# Connector_1.net
KiCad netlist of a schematic drawn in Altium Designer
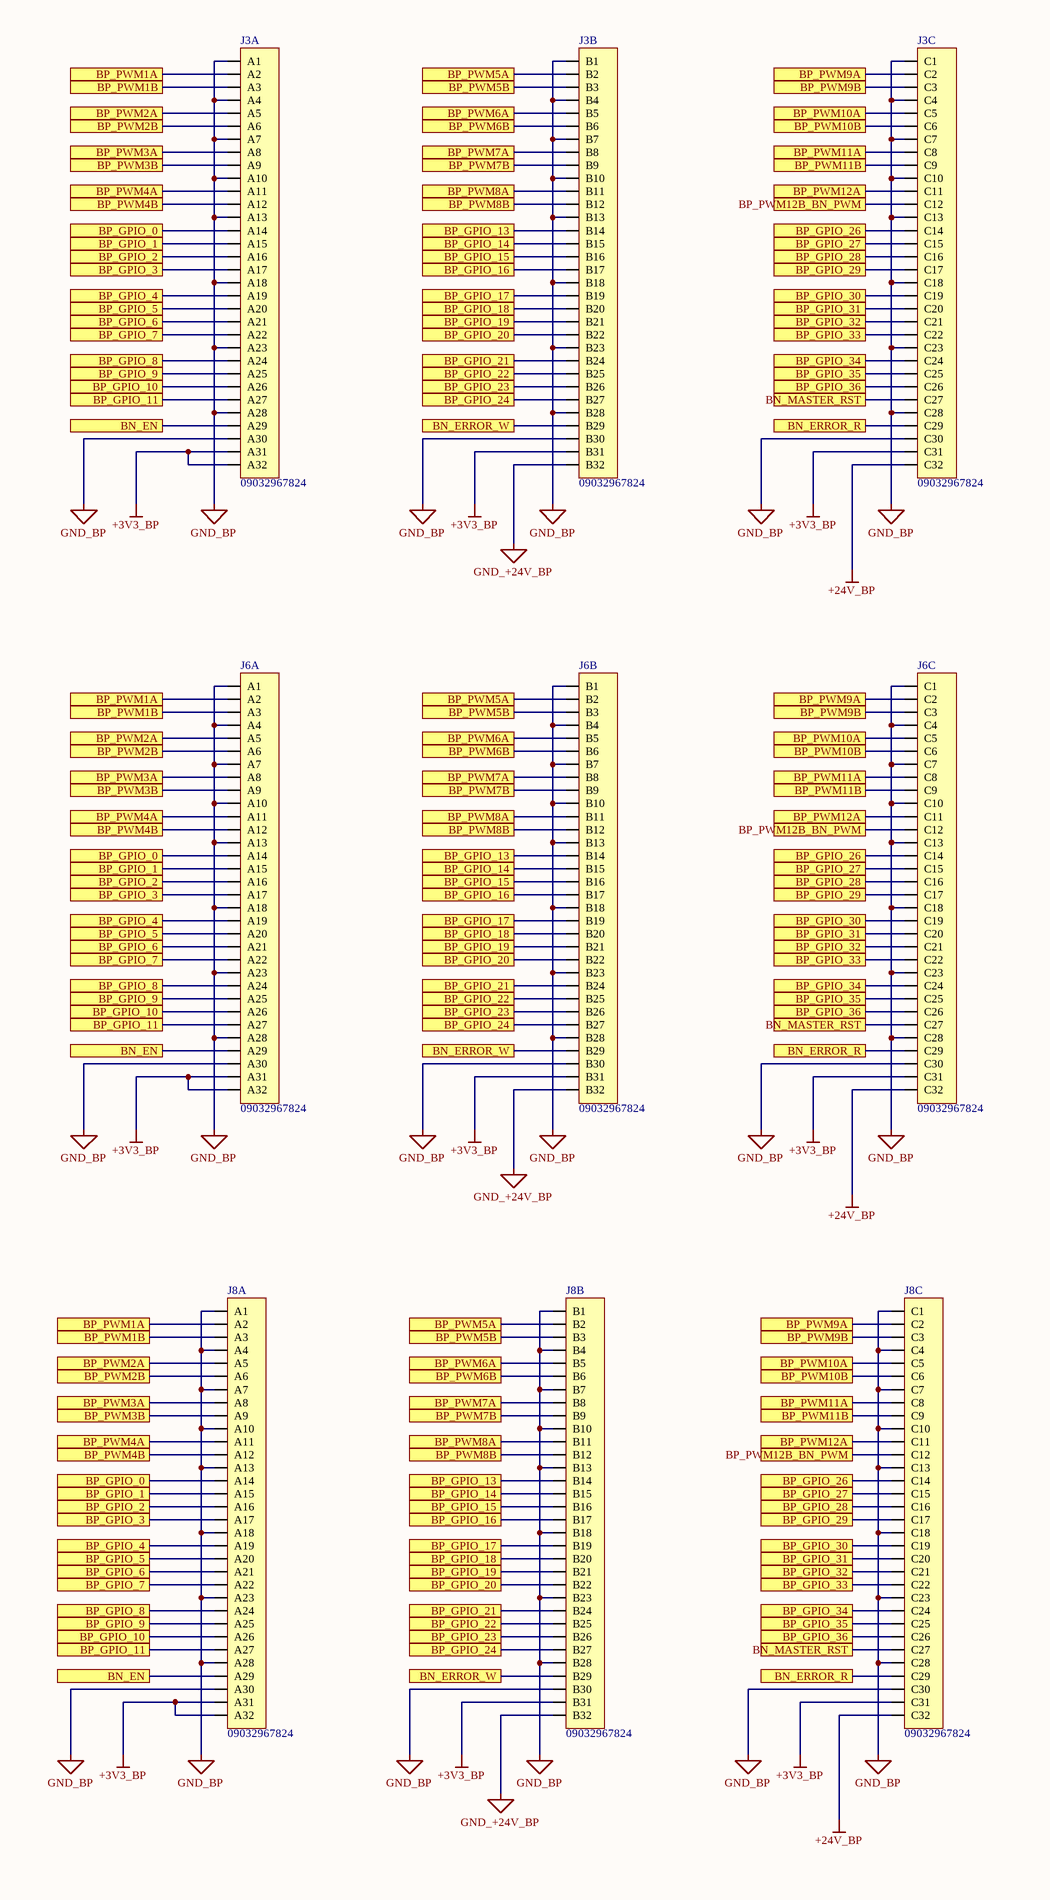
[diagram p0: Connector_1.SchDoc, left]
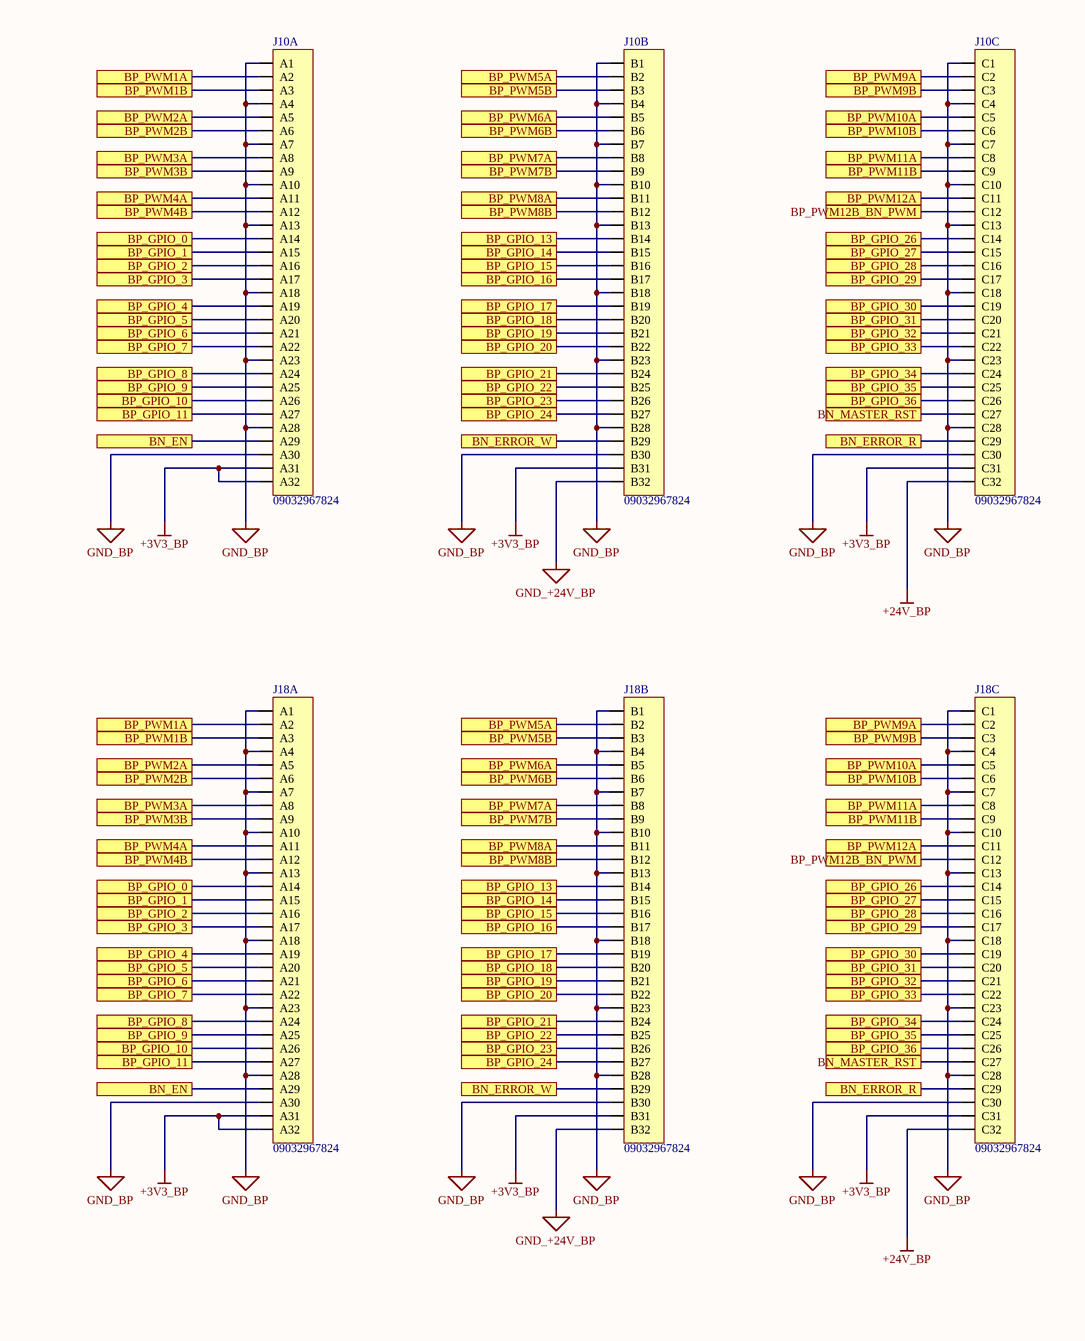
[diagram p1: Connector_1.SchDoc, right]

(export (version "E")
  (design (tool "Eeschema 10.0.6"))
  (components
    (comp (ref "J3")
      (value "09032967824")
      (footprint "DIN41612 FEM 3x32 ABC Straight")
      (description "DIN41612 FEM 3X32 ABC STRAIGHT")
      (fields (field (name "MANUFACTURER") "Harting"))
      (libsource (lib "Connector") (part "DIN41612 FEM 3X32 STRAIGHT"))
    )
    (comp (ref "J6")
      (value "09032967824")
      (footprint "DIN41612 FEM 3x32 ABC Straight")
      (description "DIN41612 FEM 3X32 ABC STRAIGHT")
      (fields (field (name "MANUFACTURER") "Harting"))
      (libsource (lib "Connector") (part "DIN41612 FEM 3X32 STRAIGHT"))
    )
    (comp (ref "J8")
      (value "09032967824")
      (footprint "DIN41612 FEM 3x32 ABC Straight")
      (description "DIN41612 FEM 3X32 ABC STRAIGHT")
      (fields (field (name "MANUFACTURER") "Harting"))
      (libsource (lib "Connector") (part "DIN41612 FEM 3X32 STRAIGHT"))
    )
    (comp (ref "J10")
      (value "09032967824")
      (footprint "DIN41612 FEM 3x32 ABC Straight")
      (description "DIN41612 FEM 3X32 ABC STRAIGHT")
      (fields (field (name "MANUFACTURER") "Harting"))
      (libsource (lib "Connector") (part "DIN41612 FEM 3X32 STRAIGHT"))
    )
    (comp (ref "J18")
      (value "09032967824")
      (footprint "DIN41612 FEM 3x32 ABC Straight")
      (description "DIN41612 FEM 3X32 ABC STRAIGHT")
      (fields (field (name "MANUFACTURER") "Harting"))
      (libsource (lib "Connector") (part "DIN41612 FEM 3X32 STRAIGHT"))
    )
  )
  (nets
    (net (code "1") (name "+3V3_BP") (class "Default")
      (node (ref "J10") (pin "A31") (pinfunction "A31_A31") (pintype "passive"))
      (node (ref "J10") (pin "A32") (pinfunction "A32_A32") (pintype "passive"))
      (node (ref "J10") (pin "B31") (pinfunction "B31_B31") (pintype "passive"))
      (node (ref "J10") (pin "C31") (pinfunction "C31_C31") (pintype "passive"))
      (node (ref "J18") (pin "A31") (pinfunction "A31_A31") (pintype "passive"))
      (node (ref "J18") (pin "A32") (pinfunction "A32_A32") (pintype "passive"))
      (node (ref "J18") (pin "B31") (pinfunction "B31_B31") (pintype "passive"))
      (node (ref "J18") (pin "C31") (pinfunction "C31_C31") (pintype "passive"))
      (node (ref "J3") (pin "A31") (pinfunction "A31_A31") (pintype "passive"))
      (node (ref "J3") (pin "A32") (pinfunction "A32_A32") (pintype "passive"))
      (node (ref "J3") (pin "B31") (pinfunction "B31_B31") (pintype "passive"))
      (node (ref "J3") (pin "C31") (pinfunction "C31_C31") (pintype "passive"))
      (node (ref "J6") (pin "A31") (pinfunction "A31_A31") (pintype "passive"))
      (node (ref "J6") (pin "A32") (pinfunction "A32_A32") (pintype "passive"))
      (node (ref "J6") (pin "B31") (pinfunction "B31_B31") (pintype "passive"))
      (node (ref "J6") (pin "C31") (pinfunction "C31_C31") (pintype "passive"))
      (node (ref "J8") (pin "A31") (pinfunction "A31_A31") (pintype "passive"))
      (node (ref "J8") (pin "A32") (pinfunction "A32_A32") (pintype "passive"))
      (node (ref "J8") (pin "B31") (pinfunction "B31_B31") (pintype "passive"))
      (node (ref "J8") (pin "C31") (pinfunction "C31_C31") (pintype "passive"))
    )
    (net (code "2") (name "+24V_BP") (class "Default")
      (node (ref "J10") (pin "C32") (pinfunction "C32_C32") (pintype "passive"))
      (node (ref "J18") (pin "C32") (pinfunction "C32_C32") (pintype "passive"))
      (node (ref "J3") (pin "C32") (pinfunction "C32_C32") (pintype "passive"))
      (node (ref "J6") (pin "C32") (pinfunction "C32_C32") (pintype "passive"))
      (node (ref "J8") (pin "C32") (pinfunction "C32_C32") (pintype "passive"))
    )
    (net (code "3") (name "/BN_EN") (class "Default")
      (node (ref "J10") (pin "A29") (pinfunction "A29_A29") (pintype "passive"))
      (node (ref "J18") (pin "A29") (pinfunction "A29_A29") (pintype "passive"))
      (node (ref "J3") (pin "A29") (pinfunction "A29_A29") (pintype "passive"))
      (node (ref "J6") (pin "A29") (pinfunction "A29_A29") (pintype "passive"))
      (node (ref "J8") (pin "A29") (pinfunction "A29_A29") (pintype "passive"))
    )
    (net (code "4") (name "/BN_ERROR_R") (class "Default")
      (node (ref "J10") (pin "C29") (pinfunction "C29_C29") (pintype "passive"))
      (node (ref "J18") (pin "C29") (pinfunction "C29_C29") (pintype "passive"))
      (node (ref "J3") (pin "C29") (pinfunction "C29_C29") (pintype "passive"))
      (node (ref "J6") (pin "C29") (pinfunction "C29_C29") (pintype "passive"))
      (node (ref "J8") (pin "C29") (pinfunction "C29_C29") (pintype "passive"))
    )
    (net (code "5") (name "/BN_ERROR_W") (class "Default")
      (node (ref "J10") (pin "B29") (pinfunction "B29_B29") (pintype "passive"))
      (node (ref "J18") (pin "B29") (pinfunction "B29_B29") (pintype "passive"))
      (node (ref "J3") (pin "B29") (pinfunction "B29_B29") (pintype "passive"))
      (node (ref "J6") (pin "B29") (pinfunction "B29_B29") (pintype "passive"))
      (node (ref "J8") (pin "B29") (pinfunction "B29_B29") (pintype "passive"))
    )
    (net (code "6") (name "/BN_MASTER_RST") (class "Default")
      (node (ref "J10") (pin "C27") (pinfunction "C27_C27") (pintype "passive"))
      (node (ref "J18") (pin "C27") (pinfunction "C27_C27") (pintype "passive"))
      (node (ref "J3") (pin "C27") (pinfunction "C27_C27") (pintype "passive"))
      (node (ref "J6") (pin "C27") (pinfunction "C27_C27") (pintype "passive"))
      (node (ref "J8") (pin "C27") (pinfunction "C27_C27") (pintype "passive"))
    )
    (net (code "7") (name "/BP_GPIO_0") (class "Default")
      (node (ref "J10") (pin "A14") (pinfunction "A14_A14") (pintype "passive"))
      (node (ref "J18") (pin "A14") (pinfunction "A14_A14") (pintype "passive"))
      (node (ref "J3") (pin "A14") (pinfunction "A14_A14") (pintype "passive"))
      (node (ref "J6") (pin "A14") (pinfunction "A14_A14") (pintype "passive"))
      (node (ref "J8") (pin "A14") (pinfunction "A14_A14") (pintype "passive"))
    )
    (net (code "8") (name "/BP_GPIO_1") (class "Default")
      (node (ref "J10") (pin "A15") (pinfunction "A15_A15") (pintype "passive"))
      (node (ref "J18") (pin "A15") (pinfunction "A15_A15") (pintype "passive"))
      (node (ref "J3") (pin "A15") (pinfunction "A15_A15") (pintype "passive"))
      (node (ref "J6") (pin "A15") (pinfunction "A15_A15") (pintype "passive"))
      (node (ref "J8") (pin "A15") (pinfunction "A15_A15") (pintype "passive"))
    )
    (net (code "9") (name "/BP_GPIO_2") (class "Default")
      (node (ref "J10") (pin "A16") (pinfunction "A16_A16") (pintype "passive"))
      (node (ref "J18") (pin "A16") (pinfunction "A16_A16") (pintype "passive"))
      (node (ref "J3") (pin "A16") (pinfunction "A16_A16") (pintype "passive"))
      (node (ref "J6") (pin "A16") (pinfunction "A16_A16") (pintype "passive"))
      (node (ref "J8") (pin "A16") (pinfunction "A16_A16") (pintype "passive"))
    )
    (net (code "10") (name "/BP_GPIO_3") (class "Default")
      (node (ref "J10") (pin "A17") (pinfunction "A17_A17") (pintype "passive"))
      (node (ref "J18") (pin "A17") (pinfunction "A17_A17") (pintype "passive"))
      (node (ref "J3") (pin "A17") (pinfunction "A17_A17") (pintype "passive"))
      (node (ref "J6") (pin "A17") (pinfunction "A17_A17") (pintype "passive"))
      (node (ref "J8") (pin "A17") (pinfunction "A17_A17") (pintype "passive"))
    )
    (net (code "11") (name "/BP_GPIO_4") (class "Default")
      (node (ref "J10") (pin "A19") (pinfunction "A19_A19") (pintype "passive"))
      (node (ref "J18") (pin "A19") (pinfunction "A19_A19") (pintype "passive"))
      (node (ref "J3") (pin "A19") (pinfunction "A19_A19") (pintype "passive"))
      (node (ref "J6") (pin "A19") (pinfunction "A19_A19") (pintype "passive"))
      (node (ref "J8") (pin "A19") (pinfunction "A19_A19") (pintype "passive"))
    )
    (net (code "12") (name "/BP_GPIO_5") (class "Default")
      (node (ref "J10") (pin "A20") (pinfunction "A20_A20") (pintype "passive"))
      (node (ref "J18") (pin "A20") (pinfunction "A20_A20") (pintype "passive"))
      (node (ref "J3") (pin "A20") (pinfunction "A20_A20") (pintype "passive"))
      (node (ref "J6") (pin "A20") (pinfunction "A20_A20") (pintype "passive"))
      (node (ref "J8") (pin "A20") (pinfunction "A20_A20") (pintype "passive"))
    )
    (net (code "13") (name "/BP_GPIO_6") (class "Default")
      (node (ref "J10") (pin "A21") (pinfunction "A21_A21") (pintype "passive"))
      (node (ref "J18") (pin "A21") (pinfunction "A21_A21") (pintype "passive"))
      (node (ref "J3") (pin "A21") (pinfunction "A21_A21") (pintype "passive"))
      (node (ref "J6") (pin "A21") (pinfunction "A21_A21") (pintype "passive"))
      (node (ref "J8") (pin "A21") (pinfunction "A21_A21") (pintype "passive"))
    )
    (net (code "14") (name "/BP_GPIO_7") (class "Default")
      (node (ref "J10") (pin "A22") (pinfunction "A22_A22") (pintype "passive"))
      (node (ref "J18") (pin "A22") (pinfunction "A22_A22") (pintype "passive"))
      (node (ref "J3") (pin "A22") (pinfunction "A22_A22") (pintype "passive"))
      (node (ref "J6") (pin "A22") (pinfunction "A22_A22") (pintype "passive"))
      (node (ref "J8") (pin "A22") (pinfunction "A22_A22") (pintype "passive"))
    )
    (net (code "15") (name "/BP_GPIO_8") (class "Default")
      (node (ref "J10") (pin "A24") (pinfunction "A24_A24") (pintype "passive"))
      (node (ref "J18") (pin "A24") (pinfunction "A24_A24") (pintype "passive"))
      (node (ref "J3") (pin "A24") (pinfunction "A24_A24") (pintype "passive"))
      (node (ref "J6") (pin "A24") (pinfunction "A24_A24") (pintype "passive"))
      (node (ref "J8") (pin "A24") (pinfunction "A24_A24") (pintype "passive"))
    )
    (net (code "16") (name "/BP_GPIO_9") (class "Default")
      (node (ref "J10") (pin "A25") (pinfunction "A25_A25") (pintype "passive"))
      (node (ref "J18") (pin "A25") (pinfunction "A25_A25") (pintype "passive"))
      (node (ref "J3") (pin "A25") (pinfunction "A25_A25") (pintype "passive"))
      (node (ref "J6") (pin "A25") (pinfunction "A25_A25") (pintype "passive"))
      (node (ref "J8") (pin "A25") (pinfunction "A25_A25") (pintype "passive"))
    )
    (net (code "17") (name "/BP_GPIO_10") (class "Default")
      (node (ref "J10") (pin "A26") (pinfunction "A26_A26") (pintype "passive"))
      (node (ref "J18") (pin "A26") (pinfunction "A26_A26") (pintype "passive"))
      (node (ref "J3") (pin "A26") (pinfunction "A26_A26") (pintype "passive"))
      (node (ref "J6") (pin "A26") (pinfunction "A26_A26") (pintype "passive"))
      (node (ref "J8") (pin "A26") (pinfunction "A26_A26") (pintype "passive"))
    )
    (net (code "18") (name "/BP_GPIO_11") (class "Default")
      (node (ref "J10") (pin "A27") (pinfunction "A27_A27") (pintype "passive"))
      (node (ref "J18") (pin "A27") (pinfunction "A27_A27") (pintype "passive"))
      (node (ref "J3") (pin "A27") (pinfunction "A27_A27") (pintype "passive"))
      (node (ref "J6") (pin "A27") (pinfunction "A27_A27") (pintype "passive"))
      (node (ref "J8") (pin "A27") (pinfunction "A27_A27") (pintype "passive"))
    )
    (net (code "19") (name "/BP_GPIO_13") (class "Default")
      (node (ref "J10") (pin "B14") (pinfunction "B14_B14") (pintype "passive"))
      (node (ref "J18") (pin "B14") (pinfunction "B14_B14") (pintype "passive"))
      (node (ref "J3") (pin "B14") (pinfunction "B14_B14") (pintype "passive"))
      (node (ref "J6") (pin "B14") (pinfunction "B14_B14") (pintype "passive"))
      (node (ref "J8") (pin "B14") (pinfunction "B14_B14") (pintype "passive"))
    )
    (net (code "20") (name "/BP_GPIO_14") (class "Default")
      (node (ref "J10") (pin "B15") (pinfunction "B15_B15") (pintype "passive"))
      (node (ref "J18") (pin "B15") (pinfunction "B15_B15") (pintype "passive"))
      (node (ref "J3") (pin "B15") (pinfunction "B15_B15") (pintype "passive"))
      (node (ref "J6") (pin "B15") (pinfunction "B15_B15") (pintype "passive"))
      (node (ref "J8") (pin "B15") (pinfunction "B15_B15") (pintype "passive"))
    )
    (net (code "21") (name "/BP_GPIO_15") (class "Default")
      (node (ref "J10") (pin "B16") (pinfunction "B16_B16") (pintype "passive"))
      (node (ref "J18") (pin "B16") (pinfunction "B16_B16") (pintype "passive"))
      (node (ref "J3") (pin "B16") (pinfunction "B16_B16") (pintype "passive"))
      (node (ref "J6") (pin "B16") (pinfunction "B16_B16") (pintype "passive"))
      (node (ref "J8") (pin "B16") (pinfunction "B16_B16") (pintype "passive"))
    )
    (net (code "22") (name "/BP_GPIO_16") (class "Default")
      (node (ref "J10") (pin "B17") (pinfunction "B17_B17") (pintype "passive"))
      (node (ref "J18") (pin "B17") (pinfunction "B17_B17") (pintype "passive"))
      (node (ref "J3") (pin "B17") (pinfunction "B17_B17") (pintype "passive"))
      (node (ref "J6") (pin "B17") (pinfunction "B17_B17") (pintype "passive"))
      (node (ref "J8") (pin "B17") (pinfunction "B17_B17") (pintype "passive"))
    )
    (net (code "23") (name "/BP_GPIO_17") (class "Default")
      (node (ref "J10") (pin "B19") (pinfunction "B19_B19") (pintype "passive"))
      (node (ref "J18") (pin "B19") (pinfunction "B19_B19") (pintype "passive"))
      (node (ref "J3") (pin "B19") (pinfunction "B19_B19") (pintype "passive"))
      (node (ref "J6") (pin "B19") (pinfunction "B19_B19") (pintype "passive"))
      (node (ref "J8") (pin "B19") (pinfunction "B19_B19") (pintype "passive"))
    )
    (net (code "24") (name "/BP_GPIO_18") (class "Default")
      (node (ref "J10") (pin "B20") (pinfunction "B20_B20") (pintype "passive"))
      (node (ref "J18") (pin "B20") (pinfunction "B20_B20") (pintype "passive"))
      (node (ref "J3") (pin "B20") (pinfunction "B20_B20") (pintype "passive"))
      (node (ref "J6") (pin "B20") (pinfunction "B20_B20") (pintype "passive"))
      (node (ref "J8") (pin "B20") (pinfunction "B20_B20") (pintype "passive"))
    )
    (net (code "25") (name "/BP_GPIO_19") (class "Default")
      (node (ref "J10") (pin "B21") (pinfunction "B21_B21") (pintype "passive"))
      (node (ref "J18") (pin "B21") (pinfunction "B21_B21") (pintype "passive"))
      (node (ref "J3") (pin "B21") (pinfunction "B21_B21") (pintype "passive"))
      (node (ref "J6") (pin "B21") (pinfunction "B21_B21") (pintype "passive"))
      (node (ref "J8") (pin "B21") (pinfunction "B21_B21") (pintype "passive"))
    )
    (net (code "26") (name "/BP_GPIO_20") (class "Default")
      (node (ref "J10") (pin "B22") (pinfunction "B22_B22") (pintype "passive"))
      (node (ref "J18") (pin "B22") (pinfunction "B22_B22") (pintype "passive"))
      (node (ref "J3") (pin "B22") (pinfunction "B22_B22") (pintype "passive"))
      (node (ref "J6") (pin "B22") (pinfunction "B22_B22") (pintype "passive"))
      (node (ref "J8") (pin "B22") (pinfunction "B22_B22") (pintype "passive"))
    )
    (net (code "27") (name "/BP_GPIO_21") (class "Default")
      (node (ref "J10") (pin "B24") (pinfunction "B24_B24") (pintype "passive"))
      (node (ref "J18") (pin "B24") (pinfunction "B24_B24") (pintype "passive"))
      (node (ref "J3") (pin "B24") (pinfunction "B24_B24") (pintype "passive"))
      (node (ref "J6") (pin "B24") (pinfunction "B24_B24") (pintype "passive"))
      (node (ref "J8") (pin "B24") (pinfunction "B24_B24") (pintype "passive"))
    )
    (net (code "28") (name "/BP_GPIO_22") (class "Default")
      (node (ref "J10") (pin "B25") (pinfunction "B25_B25") (pintype "passive"))
      (node (ref "J18") (pin "B25") (pinfunction "B25_B25") (pintype "passive"))
      (node (ref "J3") (pin "B25") (pinfunction "B25_B25") (pintype "passive"))
      (node (ref "J6") (pin "B25") (pinfunction "B25_B25") (pintype "passive"))
      (node (ref "J8") (pin "B25") (pinfunction "B25_B25") (pintype "passive"))
    )
    (net (code "29") (name "/BP_GPIO_23") (class "Default")
      (node (ref "J10") (pin "B26") (pinfunction "B26_B26") (pintype "passive"))
      (node (ref "J18") (pin "B26") (pinfunction "B26_B26") (pintype "passive"))
      (node (ref "J3") (pin "B26") (pinfunction "B26_B26") (pintype "passive"))
      (node (ref "J6") (pin "B26") (pinfunction "B26_B26") (pintype "passive"))
      (node (ref "J8") (pin "B26") (pinfunction "B26_B26") (pintype "passive"))
    )
    (net (code "30") (name "/BP_GPIO_24") (class "Default")
      (node (ref "J10") (pin "B27") (pinfunction "B27_B27") (pintype "passive"))
      (node (ref "J18") (pin "B27") (pinfunction "B27_B27") (pintype "passive"))
      (node (ref "J3") (pin "B27") (pinfunction "B27_B27") (pintype "passive"))
      (node (ref "J6") (pin "B27") (pinfunction "B27_B27") (pintype "passive"))
      (node (ref "J8") (pin "B27") (pinfunction "B27_B27") (pintype "passive"))
    )
    (net (code "31") (name "/BP_GPIO_26") (class "Default")
      (node (ref "J10") (pin "C14") (pinfunction "C14_C14") (pintype "passive"))
      (node (ref "J18") (pin "C14") (pinfunction "C14_C14") (pintype "passive"))
      (node (ref "J3") (pin "C14") (pinfunction "C14_C14") (pintype "passive"))
      (node (ref "J6") (pin "C14") (pinfunction "C14_C14") (pintype "passive"))
      (node (ref "J8") (pin "C14") (pinfunction "C14_C14") (pintype "passive"))
    )
    (net (code "32") (name "/BP_GPIO_27") (class "Default")
      (node (ref "J10") (pin "C15") (pinfunction "C15_C15") (pintype "passive"))
      (node (ref "J18") (pin "C15") (pinfunction "C15_C15") (pintype "passive"))
      (node (ref "J3") (pin "C15") (pinfunction "C15_C15") (pintype "passive"))
      (node (ref "J6") (pin "C15") (pinfunction "C15_C15") (pintype "passive"))
      (node (ref "J8") (pin "C15") (pinfunction "C15_C15") (pintype "passive"))
    )
    (net (code "33") (name "/BP_GPIO_28") (class "Default")
      (node (ref "J10") (pin "C16") (pinfunction "C16_C16") (pintype "passive"))
      (node (ref "J18") (pin "C16") (pinfunction "C16_C16") (pintype "passive"))
      (node (ref "J3") (pin "C16") (pinfunction "C16_C16") (pintype "passive"))
      (node (ref "J6") (pin "C16") (pinfunction "C16_C16") (pintype "passive"))
      (node (ref "J8") (pin "C16") (pinfunction "C16_C16") (pintype "passive"))
    )
    (net (code "34") (name "/BP_GPIO_29") (class "Default")
      (node (ref "J10") (pin "C17") (pinfunction "C17_C17") (pintype "passive"))
      (node (ref "J18") (pin "C17") (pinfunction "C17_C17") (pintype "passive"))
      (node (ref "J3") (pin "C17") (pinfunction "C17_C17") (pintype "passive"))
      (node (ref "J6") (pin "C17") (pinfunction "C17_C17") (pintype "passive"))
      (node (ref "J8") (pin "C17") (pinfunction "C17_C17") (pintype "passive"))
    )
    (net (code "35") (name "/BP_GPIO_30") (class "Default")
      (node (ref "J10") (pin "C19") (pinfunction "C19_C19") (pintype "passive"))
      (node (ref "J18") (pin "C19") (pinfunction "C19_C19") (pintype "passive"))
      (node (ref "J3") (pin "C19") (pinfunction "C19_C19") (pintype "passive"))
      (node (ref "J6") (pin "C19") (pinfunction "C19_C19") (pintype "passive"))
      (node (ref "J8") (pin "C19") (pinfunction "C19_C19") (pintype "passive"))
    )
    (net (code "36") (name "/BP_GPIO_31") (class "Default")
      (node (ref "J10") (pin "C20") (pinfunction "C20_C20") (pintype "passive"))
      (node (ref "J18") (pin "C20") (pinfunction "C20_C20") (pintype "passive"))
      (node (ref "J3") (pin "C20") (pinfunction "C20_C20") (pintype "passive"))
      (node (ref "J6") (pin "C20") (pinfunction "C20_C20") (pintype "passive"))
      (node (ref "J8") (pin "C20") (pinfunction "C20_C20") (pintype "passive"))
    )
    (net (code "37") (name "/BP_GPIO_32") (class "Default")
      (node (ref "J10") (pin "C21") (pinfunction "C21_C21") (pintype "passive"))
      (node (ref "J18") (pin "C21") (pinfunction "C21_C21") (pintype "passive"))
      (node (ref "J3") (pin "C21") (pinfunction "C21_C21") (pintype "passive"))
      (node (ref "J6") (pin "C21") (pinfunction "C21_C21") (pintype "passive"))
      (node (ref "J8") (pin "C21") (pinfunction "C21_C21") (pintype "passive"))
    )
    (net (code "38") (name "/BP_GPIO_33") (class "Default")
      (node (ref "J10") (pin "C22") (pinfunction "C22_C22") (pintype "passive"))
      (node (ref "J18") (pin "C22") (pinfunction "C22_C22") (pintype "passive"))
      (node (ref "J3") (pin "C22") (pinfunction "C22_C22") (pintype "passive"))
      (node (ref "J6") (pin "C22") (pinfunction "C22_C22") (pintype "passive"))
      (node (ref "J8") (pin "C22") (pinfunction "C22_C22") (pintype "passive"))
    )
    (net (code "39") (name "/BP_GPIO_34") (class "Default")
      (node (ref "J10") (pin "C24") (pinfunction "C24_C24") (pintype "passive"))
      (node (ref "J18") (pin "C24") (pinfunction "C24_C24") (pintype "passive"))
      (node (ref "J3") (pin "C24") (pinfunction "C24_C24") (pintype "passive"))
      (node (ref "J6") (pin "C24") (pinfunction "C24_C24") (pintype "passive"))
      (node (ref "J8") (pin "C24") (pinfunction "C24_C24") (pintype "passive"))
    )
    (net (code "40") (name "/BP_GPIO_35") (class "Default")
      (node (ref "J10") (pin "C25") (pinfunction "C25_C25") (pintype "passive"))
      (node (ref "J18") (pin "C25") (pinfunction "C25_C25") (pintype "passive"))
      (node (ref "J3") (pin "C25") (pinfunction "C25_C25") (pintype "passive"))
      (node (ref "J6") (pin "C25") (pinfunction "C25_C25") (pintype "passive"))
      (node (ref "J8") (pin "C25") (pinfunction "C25_C25") (pintype "passive"))
    )
    (net (code "41") (name "/BP_GPIO_36") (class "Default")
      (node (ref "J10") (pin "C26") (pinfunction "C26_C26") (pintype "passive"))
      (node (ref "J18") (pin "C26") (pinfunction "C26_C26") (pintype "passive"))
      (node (ref "J3") (pin "C26") (pinfunction "C26_C26") (pintype "passive"))
      (node (ref "J6") (pin "C26") (pinfunction "C26_C26") (pintype "passive"))
      (node (ref "J8") (pin "C26") (pinfunction "C26_C26") (pintype "passive"))
    )
    (net (code "42") (name "/BP_PWM1A") (class "Default")
      (node (ref "J10") (pin "A2") (pinfunction "A2_A2") (pintype "passive"))
      (node (ref "J18") (pin "A2") (pinfunction "A2_A2") (pintype "passive"))
      (node (ref "J3") (pin "A2") (pinfunction "A2_A2") (pintype "passive"))
      (node (ref "J6") (pin "A2") (pinfunction "A2_A2") (pintype "passive"))
      (node (ref "J8") (pin "A2") (pinfunction "A2_A2") (pintype "passive"))
    )
    (net (code "43") (name "/BP_PWM1B") (class "Default")
      (node (ref "J10") (pin "A3") (pinfunction "A3_A3") (pintype "passive"))
      (node (ref "J18") (pin "A3") (pinfunction "A3_A3") (pintype "passive"))
      (node (ref "J3") (pin "A3") (pinfunction "A3_A3") (pintype "passive"))
      (node (ref "J6") (pin "A3") (pinfunction "A3_A3") (pintype "passive"))
      (node (ref "J8") (pin "A3") (pinfunction "A3_A3") (pintype "passive"))
    )
    (net (code "44") (name "/BP_PWM2A") (class "Default")
      (node (ref "J10") (pin "A5") (pinfunction "A5_A5") (pintype "passive"))
      (node (ref "J18") (pin "A5") (pinfunction "A5_A5") (pintype "passive"))
      (node (ref "J3") (pin "A5") (pinfunction "A5_A5") (pintype "passive"))
      (node (ref "J6") (pin "A5") (pinfunction "A5_A5") (pintype "passive"))
      (node (ref "J8") (pin "A5") (pinfunction "A5_A5") (pintype "passive"))
    )
    (net (code "45") (name "/BP_PWM2B") (class "Default")
      (node (ref "J10") (pin "A6") (pinfunction "A6_A6") (pintype "passive"))
      (node (ref "J18") (pin "A6") (pinfunction "A6_A6") (pintype "passive"))
      (node (ref "J3") (pin "A6") (pinfunction "A6_A6") (pintype "passive"))
      (node (ref "J6") (pin "A6") (pinfunction "A6_A6") (pintype "passive"))
      (node (ref "J8") (pin "A6") (pinfunction "A6_A6") (pintype "passive"))
    )
    (net (code "46") (name "/BP_PWM3A") (class "Default")
      (node (ref "J10") (pin "A8") (pinfunction "A8_A8") (pintype "passive"))
      (node (ref "J18") (pin "A8") (pinfunction "A8_A8") (pintype "passive"))
      (node (ref "J3") (pin "A8") (pinfunction "A8_A8") (pintype "passive"))
      (node (ref "J6") (pin "A8") (pinfunction "A8_A8") (pintype "passive"))
      (node (ref "J8") (pin "A8") (pinfunction "A8_A8") (pintype "passive"))
    )
    (net (code "47") (name "/BP_PWM3B") (class "Default")
      (node (ref "J10") (pin "A9") (pinfunction "A9_A9") (pintype "passive"))
      (node (ref "J18") (pin "A9") (pinfunction "A9_A9") (pintype "passive"))
      (node (ref "J3") (pin "A9") (pinfunction "A9_A9") (pintype "passive"))
      (node (ref "J6") (pin "A9") (pinfunction "A9_A9") (pintype "passive"))
      (node (ref "J8") (pin "A9") (pinfunction "A9_A9") (pintype "passive"))
    )
    (net (code "48") (name "/BP_PWM4A") (class "Default")
      (node (ref "J10") (pin "A11") (pinfunction "A11_A11") (pintype "passive"))
      (node (ref "J18") (pin "A11") (pinfunction "A11_A11") (pintype "passive"))
      (node (ref "J3") (pin "A11") (pinfunction "A11_A11") (pintype "passive"))
      (node (ref "J6") (pin "A11") (pinfunction "A11_A11") (pintype "passive"))
      (node (ref "J8") (pin "A11") (pinfunction "A11_A11") (pintype "passive"))
    )
    (net (code "49") (name "/BP_PWM4B") (class "Default")
      (node (ref "J10") (pin "A12") (pinfunction "A12_A12") (pintype "passive"))
      (node (ref "J18") (pin "A12") (pinfunction "A12_A12") (pintype "passive"))
      (node (ref "J3") (pin "A12") (pinfunction "A12_A12") (pintype "passive"))
      (node (ref "J6") (pin "A12") (pinfunction "A12_A12") (pintype "passive"))
      (node (ref "J8") (pin "A12") (pinfunction "A12_A12") (pintype "passive"))
    )
    (net (code "50") (name "/BP_PWM5A") (class "Default")
      (node (ref "J10") (pin "B2") (pinfunction "B2_B2") (pintype "passive"))
      (node (ref "J18") (pin "B2") (pinfunction "B2_B2") (pintype "passive"))
      (node (ref "J3") (pin "B2") (pinfunction "B2_B2") (pintype "passive"))
      (node (ref "J6") (pin "B2") (pinfunction "B2_B2") (pintype "passive"))
      (node (ref "J8") (pin "B2") (pinfunction "B2_B2") (pintype "passive"))
    )
    (net (code "51") (name "/BP_PWM5B") (class "Default")
      (node (ref "J10") (pin "B3") (pinfunction "B3_B3") (pintype "passive"))
      (node (ref "J18") (pin "B3") (pinfunction "B3_B3") (pintype "passive"))
      (node (ref "J3") (pin "B3") (pinfunction "B3_B3") (pintype "passive"))
      (node (ref "J6") (pin "B3") (pinfunction "B3_B3") (pintype "passive"))
      (node (ref "J8") (pin "B3") (pinfunction "B3_B3") (pintype "passive"))
    )
    (net (code "52") (name "/BP_PWM6A") (class "Default")
      (node (ref "J10") (pin "B5") (pinfunction "B5_B5") (pintype "passive"))
      (node (ref "J18") (pin "B5") (pinfunction "B5_B5") (pintype "passive"))
      (node (ref "J3") (pin "B5") (pinfunction "B5_B5") (pintype "passive"))
      (node (ref "J6") (pin "B5") (pinfunction "B5_B5") (pintype "passive"))
      (node (ref "J8") (pin "B5") (pinfunction "B5_B5") (pintype "passive"))
    )
    (net (code "53") (name "/BP_PWM6B") (class "Default")
      (node (ref "J10") (pin "B6") (pinfunction "B6_B6") (pintype "passive"))
      (node (ref "J18") (pin "B6") (pinfunction "B6_B6") (pintype "passive"))
      (node (ref "J3") (pin "B6") (pinfunction "B6_B6") (pintype "passive"))
      (node (ref "J6") (pin "B6") (pinfunction "B6_B6") (pintype "passive"))
      (node (ref "J8") (pin "B6") (pinfunction "B6_B6") (pintype "passive"))
    )
    (net (code "54") (name "/BP_PWM7A") (class "Default")
      (node (ref "J10") (pin "B8") (pinfunction "B8_B8") (pintype "passive"))
      (node (ref "J18") (pin "B8") (pinfunction "B8_B8") (pintype "passive"))
      (node (ref "J3") (pin "B8") (pinfunction "B8_B8") (pintype "passive"))
      (node (ref "J6") (pin "B8") (pinfunction "B8_B8") (pintype "passive"))
      (node (ref "J8") (pin "B8") (pinfunction "B8_B8") (pintype "passive"))
    )
    (net (code "55") (name "/BP_PWM7B") (class "Default")
      (node (ref "J10") (pin "B9") (pinfunction "B9_B9") (pintype "passive"))
      (node (ref "J18") (pin "B9") (pinfunction "B9_B9") (pintype "passive"))
      (node (ref "J3") (pin "B9") (pinfunction "B9_B9") (pintype "passive"))
      (node (ref "J6") (pin "B9") (pinfunction "B9_B9") (pintype "passive"))
      (node (ref "J8") (pin "B9") (pinfunction "B9_B9") (pintype "passive"))
    )
    (net (code "56") (name "/BP_PWM8A") (class "Default")
      (node (ref "J10") (pin "B11") (pinfunction "B11_B11") (pintype "passive"))
      (node (ref "J18") (pin "B11") (pinfunction "B11_B11") (pintype "passive"))
      (node (ref "J3") (pin "B11") (pinfunction "B11_B11") (pintype "passive"))
      (node (ref "J6") (pin "B11") (pinfunction "B11_B11") (pintype "passive"))
      (node (ref "J8") (pin "B11") (pinfunction "B11_B11") (pintype "passive"))
    )
    (net (code "57") (name "/BP_PWM8B") (class "Default")
      (node (ref "J10") (pin "B12") (pinfunction "B12_B12") (pintype "passive"))
      (node (ref "J18") (pin "B12") (pinfunction "B12_B12") (pintype "passive"))
      (node (ref "J3") (pin "B12") (pinfunction "B12_B12") (pintype "passive"))
      (node (ref "J6") (pin "B12") (pinfunction "B12_B12") (pintype "passive"))
      (node (ref "J8") (pin "B12") (pinfunction "B12_B12") (pintype "passive"))
    )
    (net (code "58") (name "/BP_PWM9A") (class "Default")
      (node (ref "J10") (pin "C2") (pinfunction "C2_C2") (pintype "passive"))
      (node (ref "J18") (pin "C2") (pinfunction "C2_C2") (pintype "passive"))
      (node (ref "J3") (pin "C2") (pinfunction "C2_C2") (pintype "passive"))
      (node (ref "J6") (pin "C2") (pinfunction "C2_C2") (pintype "passive"))
      (node (ref "J8") (pin "C2") (pinfunction "C2_C2") (pintype "passive"))
    )
    (net (code "59") (name "/BP_PWM9B") (class "Default")
      (node (ref "J10") (pin "C3") (pinfunction "C3_C3") (pintype "passive"))
      (node (ref "J18") (pin "C3") (pinfunction "C3_C3") (pintype "passive"))
      (node (ref "J3") (pin "C3") (pinfunction "C3_C3") (pintype "passive"))
      (node (ref "J6") (pin "C3") (pinfunction "C3_C3") (pintype "passive"))
      (node (ref "J8") (pin "C3") (pinfunction "C3_C3") (pintype "passive"))
    )
    (net (code "60") (name "/BP_PWM10A") (class "Default")
      (node (ref "J10") (pin "C5") (pinfunction "C5_C5") (pintype "passive"))
      (node (ref "J18") (pin "C5") (pinfunction "C5_C5") (pintype "passive"))
      (node (ref "J3") (pin "C5") (pinfunction "C5_C5") (pintype "passive"))
      (node (ref "J6") (pin "C5") (pinfunction "C5_C5") (pintype "passive"))
      (node (ref "J8") (pin "C5") (pinfunction "C5_C5") (pintype "passive"))
    )
    (net (code "61") (name "/BP_PWM10B") (class "Default")
      (node (ref "J10") (pin "C6") (pinfunction "C6_C6") (pintype "passive"))
      (node (ref "J18") (pin "C6") (pinfunction "C6_C6") (pintype "passive"))
      (node (ref "J3") (pin "C6") (pinfunction "C6_C6") (pintype "passive"))
      (node (ref "J6") (pin "C6") (pinfunction "C6_C6") (pintype "passive"))
      (node (ref "J8") (pin "C6") (pinfunction "C6_C6") (pintype "passive"))
    )
    (net (code "62") (name "/BP_PWM11A") (class "Default")
      (node (ref "J10") (pin "C8") (pinfunction "C8_C8") (pintype "passive"))
      (node (ref "J18") (pin "C8") (pinfunction "C8_C8") (pintype "passive"))
      (node (ref "J3") (pin "C8") (pinfunction "C8_C8") (pintype "passive"))
      (node (ref "J6") (pin "C8") (pinfunction "C8_C8") (pintype "passive"))
      (node (ref "J8") (pin "C8") (pinfunction "C8_C8") (pintype "passive"))
    )
    (net (code "63") (name "/BP_PWM11B") (class "Default")
      (node (ref "J10") (pin "C9") (pinfunction "C9_C9") (pintype "passive"))
      (node (ref "J18") (pin "C9") (pinfunction "C9_C9") (pintype "passive"))
      (node (ref "J3") (pin "C9") (pinfunction "C9_C9") (pintype "passive"))
      (node (ref "J6") (pin "C9") (pinfunction "C9_C9") (pintype "passive"))
      (node (ref "J8") (pin "C9") (pinfunction "C9_C9") (pintype "passive"))
    )
    (net (code "64") (name "/BP_PWM12A") (class "Default")
      (node (ref "J10") (pin "C11") (pinfunction "C11_C11") (pintype "passive"))
      (node (ref "J18") (pin "C11") (pinfunction "C11_C11") (pintype "passive"))
      (node (ref "J3") (pin "C11") (pinfunction "C11_C11") (pintype "passive"))
      (node (ref "J6") (pin "C11") (pinfunction "C11_C11") (pintype "passive"))
      (node (ref "J8") (pin "C11") (pinfunction "C11_C11") (pintype "passive"))
    )
    (net (code "65") (name "/BP_PWM12B_BN_PWM") (class "Default")
      (node (ref "J10") (pin "C12") (pinfunction "C12_C12") (pintype "passive"))
      (node (ref "J18") (pin "C12") (pinfunction "C12_C12") (pintype "passive"))
      (node (ref "J3") (pin "C12") (pinfunction "C12_C12") (pintype "passive"))
      (node (ref "J6") (pin "C12") (pinfunction "C12_C12") (pintype "passive"))
      (node (ref "J8") (pin "C12") (pinfunction "C12_C12") (pintype "passive"))
    )
    (net (code "66") (name "GND_+24V_BP") (class "Default")
      (node (ref "J10") (pin "B32") (pinfunction "B32_B32") (pintype "passive"))
      (node (ref "J18") (pin "B32") (pinfunction "B32_B32") (pintype "passive"))
      (node (ref "J3") (pin "B32") (pinfunction "B32_B32") (pintype "passive"))
      (node (ref "J6") (pin "B32") (pinfunction "B32_B32") (pintype "passive"))
      (node (ref "J8") (pin "B32") (pinfunction "B32_B32") (pintype "passive"))
    )
    (net (code "67") (name "GND_BP") (class "Default")
      (node (ref "J10") (pin "A1") (pinfunction "A1_A1") (pintype "passive"))
      (node (ref "J10") (pin "A10") (pinfunction "A10_A10") (pintype "passive"))
      (node (ref "J10") (pin "A13") (pinfunction "A13_A13") (pintype "passive"))
      (node (ref "J10") (pin "A18") (pinfunction "A18_A18") (pintype "passive"))
      (node (ref "J10") (pin "A23") (pinfunction "A23_A23") (pintype "passive"))
      (node (ref "J10") (pin "A28") (pinfunction "A28_A28") (pintype "passive"))
      (node (ref "J10") (pin "A30") (pinfunction "A30_A30") (pintype "passive"))
      (node (ref "J10") (pin "A4") (pinfunction "A4_A4") (pintype "passive"))
      (node (ref "J10") (pin "A7") (pinfunction "A7_A7") (pintype "passive"))
      (node (ref "J10") (pin "B1") (pinfunction "B1_B1") (pintype "passive"))
      (node (ref "J10") (pin "B10") (pinfunction "B10_B10") (pintype "passive"))
      (node (ref "J10") (pin "B13") (pinfunction "B13_B13") (pintype "passive"))
      (node (ref "J10") (pin "B18") (pinfunction "B18_B18") (pintype "passive"))
      (node (ref "J10") (pin "B23") (pinfunction "B23_B23") (pintype "passive"))
      (node (ref "J10") (pin "B28") (pinfunction "B28_B28") (pintype "passive"))
      (node (ref "J10") (pin "B30") (pinfunction "B30_B30") (pintype "passive"))
      (node (ref "J10") (pin "B4") (pinfunction "B4_B4") (pintype "passive"))
      (node (ref "J10") (pin "B7") (pinfunction "B7_B7") (pintype "passive"))
      (node (ref "J10") (pin "C1") (pinfunction "C1_C1") (pintype "passive"))
      (node (ref "J10") (pin "C10") (pinfunction "C10_C10") (pintype "passive"))
      (node (ref "J10") (pin "C13") (pinfunction "C13_C13") (pintype "passive"))
      (node (ref "J10") (pin "C18") (pinfunction "C18_C18") (pintype "passive"))
      (node (ref "J10") (pin "C23") (pinfunction "C23_C23") (pintype "passive"))
      (node (ref "J10") (pin "C28") (pinfunction "C28_C28") (pintype "passive"))
      (node (ref "J10") (pin "C30") (pinfunction "C30_C30") (pintype "passive"))
      (node (ref "J10") (pin "C4") (pinfunction "C4_C4") (pintype "passive"))
      (node (ref "J10") (pin "C7") (pinfunction "C7_C7") (pintype "passive"))
      (node (ref "J18") (pin "A1") (pinfunction "A1_A1") (pintype "passive"))
      (node (ref "J18") (pin "A10") (pinfunction "A10_A10") (pintype "passive"))
      (node (ref "J18") (pin "A13") (pinfunction "A13_A13") (pintype "passive"))
      (node (ref "J18") (pin "A18") (pinfunction "A18_A18") (pintype "passive"))
      (node (ref "J18") (pin "A23") (pinfunction "A23_A23") (pintype "passive"))
      (node (ref "J18") (pin "A28") (pinfunction "A28_A28") (pintype "passive"))
      (node (ref "J18") (pin "A30") (pinfunction "A30_A30") (pintype "passive"))
      (node (ref "J18") (pin "A4") (pinfunction "A4_A4") (pintype "passive"))
      (node (ref "J18") (pin "A7") (pinfunction "A7_A7") (pintype "passive"))
      (node (ref "J18") (pin "B1") (pinfunction "B1_B1") (pintype "passive"))
      (node (ref "J18") (pin "B10") (pinfunction "B10_B10") (pintype "passive"))
      (node (ref "J18") (pin "B13") (pinfunction "B13_B13") (pintype "passive"))
      (node (ref "J18") (pin "B18") (pinfunction "B18_B18") (pintype "passive"))
      (node (ref "J18") (pin "B23") (pinfunction "B23_B23") (pintype "passive"))
      (node (ref "J18") (pin "B28") (pinfunction "B28_B28") (pintype "passive"))
      (node (ref "J18") (pin "B30") (pinfunction "B30_B30") (pintype "passive"))
      (node (ref "J18") (pin "B4") (pinfunction "B4_B4") (pintype "passive"))
      (node (ref "J18") (pin "B7") (pinfunction "B7_B7") (pintype "passive"))
      (node (ref "J18") (pin "C1") (pinfunction "C1_C1") (pintype "passive"))
      (node (ref "J18") (pin "C10") (pinfunction "C10_C10") (pintype "passive"))
      (node (ref "J18") (pin "C13") (pinfunction "C13_C13") (pintype "passive"))
      (node (ref "J18") (pin "C18") (pinfunction "C18_C18") (pintype "passive"))
      (node (ref "J18") (pin "C23") (pinfunction "C23_C23") (pintype "passive"))
      (node (ref "J18") (pin "C28") (pinfunction "C28_C28") (pintype "passive"))
      (node (ref "J18") (pin "C30") (pinfunction "C30_C30") (pintype "passive"))
      (node (ref "J18") (pin "C4") (pinfunction "C4_C4") (pintype "passive"))
      (node (ref "J18") (pin "C7") (pinfunction "C7_C7") (pintype "passive"))
      (node (ref "J3") (pin "A1") (pinfunction "A1_A1") (pintype "passive"))
      (node (ref "J3") (pin "A10") (pinfunction "A10_A10") (pintype "passive"))
      (node (ref "J3") (pin "A13") (pinfunction "A13_A13") (pintype "passive"))
      (node (ref "J3") (pin "A18") (pinfunction "A18_A18") (pintype "passive"))
      (node (ref "J3") (pin "A23") (pinfunction "A23_A23") (pintype "passive"))
      (node (ref "J3") (pin "A28") (pinfunction "A28_A28") (pintype "passive"))
      (node (ref "J3") (pin "A30") (pinfunction "A30_A30") (pintype "passive"))
      (node (ref "J3") (pin "A4") (pinfunction "A4_A4") (pintype "passive"))
      (node (ref "J3") (pin "A7") (pinfunction "A7_A7") (pintype "passive"))
      (node (ref "J3") (pin "B1") (pinfunction "B1_B1") (pintype "passive"))
      (node (ref "J3") (pin "B10") (pinfunction "B10_B10") (pintype "passive"))
      (node (ref "J3") (pin "B13") (pinfunction "B13_B13") (pintype "passive"))
      (node (ref "J3") (pin "B18") (pinfunction "B18_B18") (pintype "passive"))
      (node (ref "J3") (pin "B23") (pinfunction "B23_B23") (pintype "passive"))
      (node (ref "J3") (pin "B28") (pinfunction "B28_B28") (pintype "passive"))
      (node (ref "J3") (pin "B30") (pinfunction "B30_B30") (pintype "passive"))
      (node (ref "J3") (pin "B4") (pinfunction "B4_B4") (pintype "passive"))
      (node (ref "J3") (pin "B7") (pinfunction "B7_B7") (pintype "passive"))
      (node (ref "J3") (pin "C1") (pinfunction "C1_C1") (pintype "passive"))
      (node (ref "J3") (pin "C10") (pinfunction "C10_C10") (pintype "passive"))
      (node (ref "J3") (pin "C13") (pinfunction "C13_C13") (pintype "passive"))
      (node (ref "J3") (pin "C18") (pinfunction "C18_C18") (pintype "passive"))
      (node (ref "J3") (pin "C23") (pinfunction "C23_C23") (pintype "passive"))
      (node (ref "J3") (pin "C28") (pinfunction "C28_C28") (pintype "passive"))
      (node (ref "J3") (pin "C30") (pinfunction "C30_C30") (pintype "passive"))
      (node (ref "J3") (pin "C4") (pinfunction "C4_C4") (pintype "passive"))
      (node (ref "J3") (pin "C7") (pinfunction "C7_C7") (pintype "passive"))
      (node (ref "J6") (pin "A1") (pinfunction "A1_A1") (pintype "passive"))
      (node (ref "J6") (pin "A10") (pinfunction "A10_A10") (pintype "passive"))
      (node (ref "J6") (pin "A13") (pinfunction "A13_A13") (pintype "passive"))
      (node (ref "J6") (pin "A18") (pinfunction "A18_A18") (pintype "passive"))
      (node (ref "J6") (pin "A23") (pinfunction "A23_A23") (pintype "passive"))
      (node (ref "J6") (pin "A28") (pinfunction "A28_A28") (pintype "passive"))
      (node (ref "J6") (pin "A30") (pinfunction "A30_A30") (pintype "passive"))
      (node (ref "J6") (pin "A4") (pinfunction "A4_A4") (pintype "passive"))
      (node (ref "J6") (pin "A7") (pinfunction "A7_A7") (pintype "passive"))
      (node (ref "J6") (pin "B1") (pinfunction "B1_B1") (pintype "passive"))
      (node (ref "J6") (pin "B10") (pinfunction "B10_B10") (pintype "passive"))
      (node (ref "J6") (pin "B13") (pinfunction "B13_B13") (pintype "passive"))
      (node (ref "J6") (pin "B18") (pinfunction "B18_B18") (pintype "passive"))
      (node (ref "J6") (pin "B23") (pinfunction "B23_B23") (pintype "passive"))
      (node (ref "J6") (pin "B28") (pinfunction "B28_B28") (pintype "passive"))
      (node (ref "J6") (pin "B30") (pinfunction "B30_B30") (pintype "passive"))
      (node (ref "J6") (pin "B4") (pinfunction "B4_B4") (pintype "passive"))
      (node (ref "J6") (pin "B7") (pinfunction "B7_B7") (pintype "passive"))
      (node (ref "J6") (pin "C1") (pinfunction "C1_C1") (pintype "passive"))
      (node (ref "J6") (pin "C10") (pinfunction "C10_C10") (pintype "passive"))
      (node (ref "J6") (pin "C13") (pinfunction "C13_C13") (pintype "passive"))
      (node (ref "J6") (pin "C18") (pinfunction "C18_C18") (pintype "passive"))
      (node (ref "J6") (pin "C23") (pinfunction "C23_C23") (pintype "passive"))
      (node (ref "J6") (pin "C28") (pinfunction "C28_C28") (pintype "passive"))
      (node (ref "J6") (pin "C30") (pinfunction "C30_C30") (pintype "passive"))
      (node (ref "J6") (pin "C4") (pinfunction "C4_C4") (pintype "passive"))
      (node (ref "J6") (pin "C7") (pinfunction "C7_C7") (pintype "passive"))
      (node (ref "J8") (pin "A1") (pinfunction "A1_A1") (pintype "passive"))
      (node (ref "J8") (pin "A10") (pinfunction "A10_A10") (pintype "passive"))
      (node (ref "J8") (pin "A13") (pinfunction "A13_A13") (pintype "passive"))
      (node (ref "J8") (pin "A18") (pinfunction "A18_A18") (pintype "passive"))
      (node (ref "J8") (pin "A23") (pinfunction "A23_A23") (pintype "passive"))
      (node (ref "J8") (pin "A28") (pinfunction "A28_A28") (pintype "passive"))
      (node (ref "J8") (pin "A30") (pinfunction "A30_A30") (pintype "passive"))
      (node (ref "J8") (pin "A4") (pinfunction "A4_A4") (pintype "passive"))
      (node (ref "J8") (pin "A7") (pinfunction "A7_A7") (pintype "passive"))
      (node (ref "J8") (pin "B1") (pinfunction "B1_B1") (pintype "passive"))
      (node (ref "J8") (pin "B10") (pinfunction "B10_B10") (pintype "passive"))
      (node (ref "J8") (pin "B13") (pinfunction "B13_B13") (pintype "passive"))
      (node (ref "J8") (pin "B18") (pinfunction "B18_B18") (pintype "passive"))
      (node (ref "J8") (pin "B23") (pinfunction "B23_B23") (pintype "passive"))
      (node (ref "J8") (pin "B28") (pinfunction "B28_B28") (pintype "passive"))
      (node (ref "J8") (pin "B30") (pinfunction "B30_B30") (pintype "passive"))
      (node (ref "J8") (pin "B4") (pinfunction "B4_B4") (pintype "passive"))
      (node (ref "J8") (pin "B7") (pinfunction "B7_B7") (pintype "passive"))
      (node (ref "J8") (pin "C1") (pinfunction "C1_C1") (pintype "passive"))
      (node (ref "J8") (pin "C10") (pinfunction "C10_C10") (pintype "passive"))
      (node (ref "J8") (pin "C13") (pinfunction "C13_C13") (pintype "passive"))
      (node (ref "J8") (pin "C18") (pinfunction "C18_C18") (pintype "passive"))
      (node (ref "J8") (pin "C23") (pinfunction "C23_C23") (pintype "passive"))
      (node (ref "J8") (pin "C28") (pinfunction "C28_C28") (pintype "passive"))
      (node (ref "J8") (pin "C30") (pinfunction "C30_C30") (pintype "passive"))
      (node (ref "J8") (pin "C4") (pinfunction "C4_C4") (pintype "passive"))
      (node (ref "J8") (pin "C7") (pinfunction "C7_C7") (pintype "passive"))
    )
  )
)
